# SCH_Moisture_Sensorv1_2022-10-20.net
KiCad netlist of a schematic drawn in EasyEDA
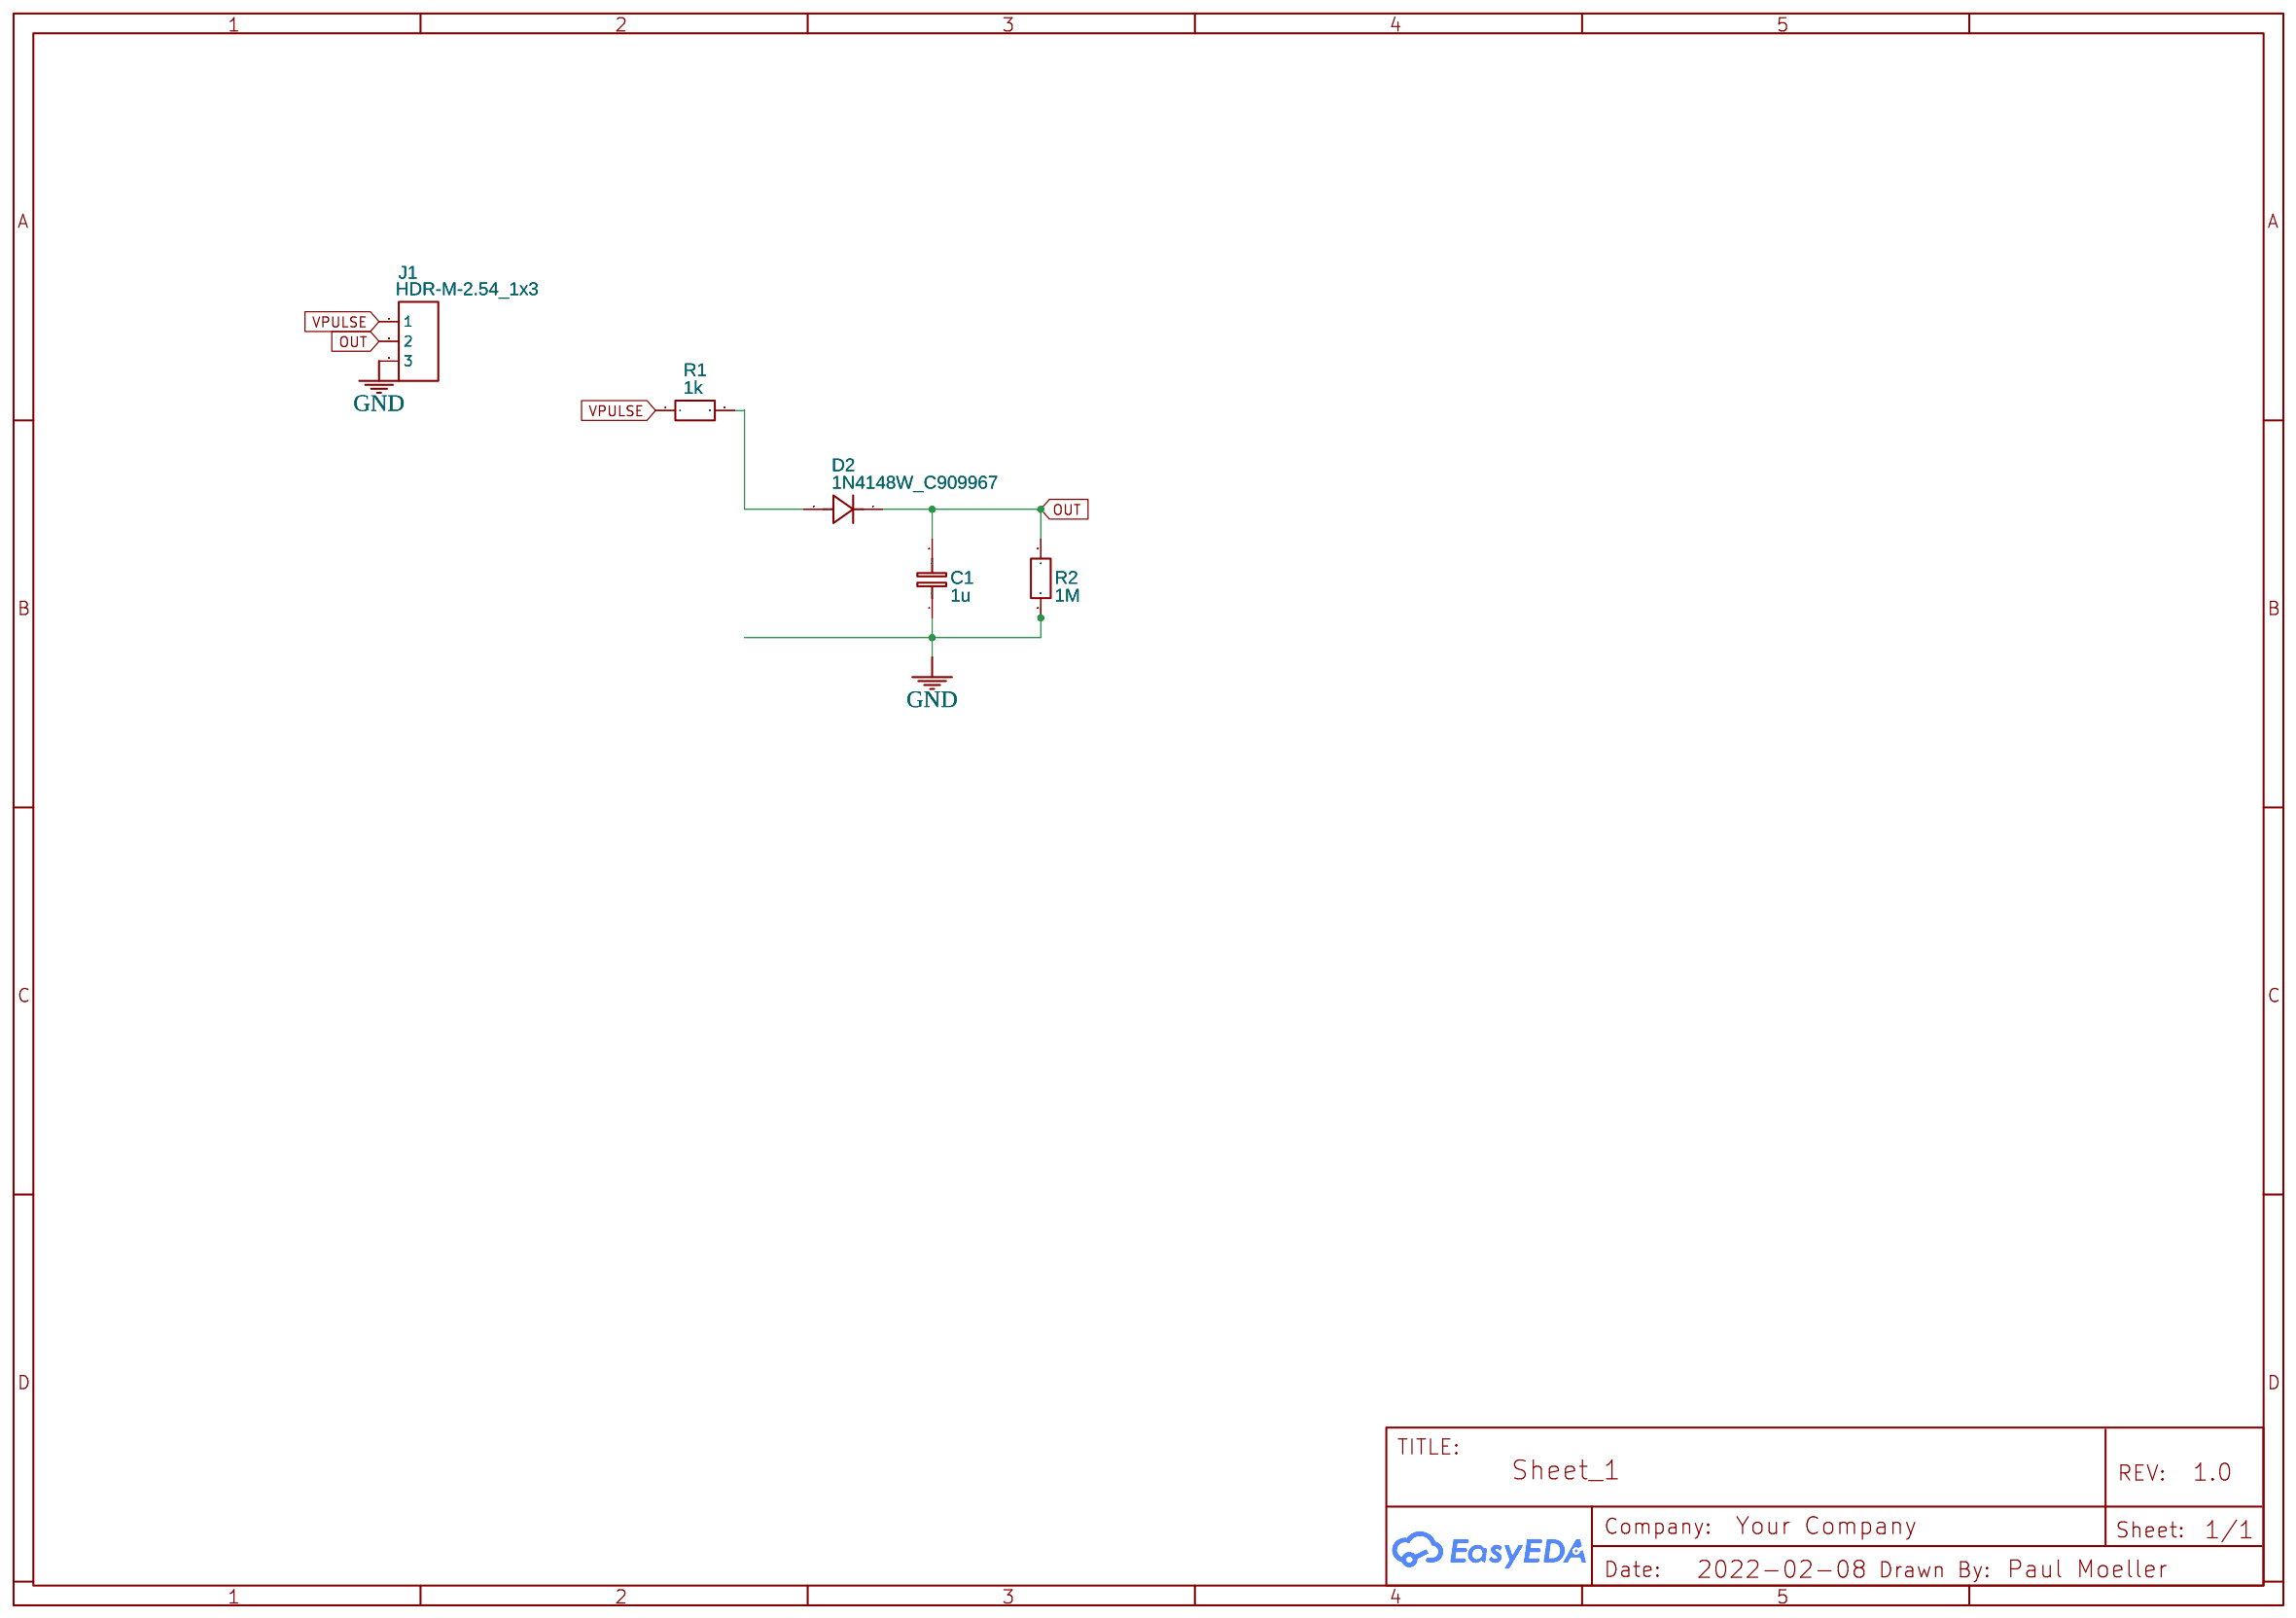
[diagram p0: schematic sheet]

(export (version "E")
  (design (tool "Eeschema 10.0.6"))
  (components
    (comp (ref "C1") (value "1u") (libsource (lib "") (part "C_0805_EU")))
    (comp (ref "D2")
      (value "1N4148W_C909967")
      (fields (field (name "BOM_Manufacturer Part") "1N4148W") (field (name "BOM_Supplier Part") "C909967"))
      (libsource (lib "") (part "1N4148W_C909967"))
    )
    (comp (ref "J1")
      (value "HDR-M-2.54_1x3")
      (fields (field (name "BOM_Supplier Part") "C180248"))
      (libsource (lib "") (part "HDR-M-2.54_1x3"))
    )
    (comp (ref "R1") (value "1k") (libsource (lib "") (part "R_0805_EU")))
    (comp (ref "R2") (value "1M") (libsource (lib "") (part "R_0805_EU_1")))
  )
  (nets
    (net (code "1") (name "GND") (class "Default")
      (node (ref "C1") (pin "1") (pinfunction "1_1") (pintype "unspecified"))
      (node (ref "J1") (pin "3") (pinfunction "3_3") (pintype "input"))
      (node (ref "R2") (pin "1") (pinfunction "1_1") (pintype "unspecified"))
    )
    (net (code "2") (name "Net-(D2-A)") (class "Default")
      (node (ref "D2") (pin "2") (pinfunction "A_2") (pintype "unspecified"))
      (node (ref "R1") (pin "2") (pinfunction "2_2") (pintype "unspecified"))
    )
    (net (code "3") (name "OUT") (class "Default")
      (node (ref "C1") (pin "2") (pinfunction "2_2") (pintype "unspecified"))
      (node (ref "D2") (pin "1") (pinfunction "K_1") (pintype "unspecified"))
      (node (ref "J1") (pin "2") (pinfunction "2_2") (pintype "input"))
      (node (ref "R2") (pin "2") (pinfunction "2_2") (pintype "unspecified"))
    )
    (net (code "4") (name "VPULSE") (class "Default")
      (node (ref "J1") (pin "1") (pinfunction "1_1") (pintype "input"))
      (node (ref "R1") (pin "1") (pinfunction "1_1") (pintype "unspecified"))
    )
  )
)
